# hm11.net
KiCad netlist of a schematic drawn in EAGLE
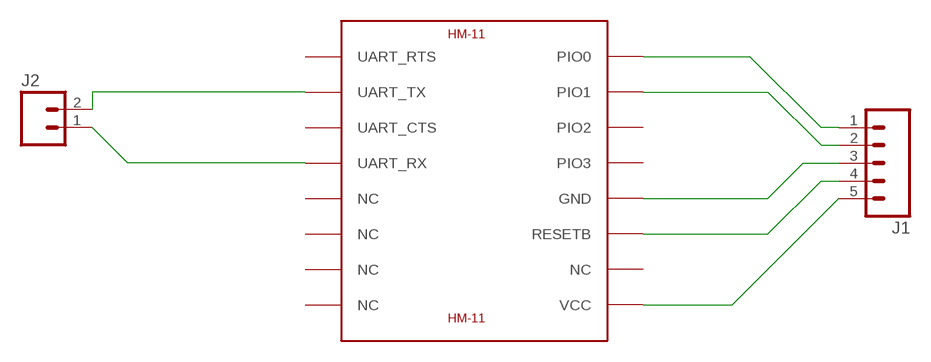
[diagram p0: schematic, sheet 1]

(export (version "E")
  (design (tool "Eeschema 10.0.6"))
  (components
    (comp (ref "J1")
      (value "M05PTH_LONGPADS")
      (footprint "eagle-import:1X05_LONGPADS")
      (libsource (lib "eagle-import") (part "M05PTH_LONGPADS"))
    )
    (comp (ref "J2")
      (value "M02PTH3")
      (footprint "eagle-import:1X02_LONGPADS")
      (libsource (lib "eagle-import") (part "M02PTH3"))
    )
    (comp (ref "U$1")
      (value "HM-11")
      (footprint "eagle-import:HM-11")
      (libsource (lib "eagle-import") (part "HM-11"))
    )
  )
  (nets
    (net (code "1") (name "Net-(J1-Pad1)") (class "Default")
      (node (ref "J1") (pin "1") (pinfunction "1_1") (pintype "passive"))
      (node (ref "U$1") (pin "PIO0") (pinfunction "PIO0_PIO0") (pintype "bidirectional"))
    )
    (net (code "2") (name "Net-(J1-Pad2)") (class "Default")
      (node (ref "J1") (pin "2") (pinfunction "2_2") (pintype "passive"))
      (node (ref "U$1") (pin "PIO1") (pinfunction "PIO1_PIO1") (pintype "bidirectional"))
    )
    (net (code "3") (name "Net-(J1-Pad3)") (class "Default")
      (node (ref "J1") (pin "3") (pinfunction "3_3") (pintype "passive"))
      (node (ref "U$1") (pin "GND") (pinfunction "GND_GND") (pintype "bidirectional"))
    )
    (net (code "4") (name "Net-(J1-Pad4)") (class "Default")
      (node (ref "J1") (pin "4") (pinfunction "4_4") (pintype "passive"))
      (node (ref "U$1") (pin "RESETB") (pinfunction "RESETB_RESETB") (pintype "bidirectional"))
    )
    (net (code "5") (name "Net-(J1-Pad5)") (class "Default")
      (node (ref "J1") (pin "5") (pinfunction "5_5") (pintype "passive"))
      (node (ref "U$1") (pin "VCC") (pinfunction "VCC_VCC") (pintype "bidirectional"))
    )
    (net (code "6") (name "Net-(J2-Pad1)") (class "Default")
      (node (ref "J2") (pin "1") (pinfunction "1_1") (pintype "passive"))
      (node (ref "U$1") (pin "UART_RX") (pinfunction "UART_RX_UART_RX") (pintype "bidirectional"))
    )
    (net (code "7") (name "Net-(J2-Pad2)") (class "Default")
      (node (ref "J2") (pin "2") (pinfunction "2_2") (pintype "passive"))
      (node (ref "U$1") (pin "UART_TX") (pinfunction "UART_TX_UART_TX") (pintype "bidirectional"))
    )
    (net (code "8") (name "unconnected-(U$1-NC-PadNC@5)") (class "Default")
      (node (ref "U$1") (pin "NC@5") (pinfunction "NC_NC@5") (pintype "bidirectional"))
    )
    (net (code "9") (name "unconnected-(U$1-NC-PadNC@6)") (class "Default")
      (node (ref "U$1") (pin "NC@6") (pinfunction "NC_NC@6") (pintype "bidirectional"))
    )
    (net (code "10") (name "unconnected-(U$1-NC-PadNC@7)") (class "Default")
      (node (ref "U$1") (pin "NC@7") (pinfunction "NC_NC@7") (pintype "bidirectional"))
    )
    (net (code "11") (name "unconnected-(U$1-NC-PadNC@8)") (class "Default")
      (node (ref "U$1") (pin "NC@8") (pinfunction "NC_NC@8") (pintype "bidirectional"))
    )
    (net (code "12") (name "unconnected-(U$1-NC-PadNC@10)") (class "Default")
      (node (ref "U$1") (pin "NC@10") (pinfunction "NC_NC@10") (pintype "bidirectional"))
    )
    (net (code "13") (name "unconnected-(U$1-PadPIO2)") (class "Default")
      (node (ref "U$1") (pin "PIO2") (pinfunction "PIO2_PIO2") (pintype "bidirectional"))
    )
    (net (code "14") (name "unconnected-(U$1-PadPIO3)") (class "Default")
      (node (ref "U$1") (pin "PIO3") (pinfunction "PIO3_PIO3") (pintype "bidirectional"))
    )
    (net (code "15") (name "unconnected-(U$1-PadUART_CTS)") (class "Default")
      (node (ref "U$1") (pin "UART_CTS") (pinfunction "UART_CTS_UART_CTS") (pintype "bidirectional"))
    )
    (net (code "16") (name "unconnected-(U$1-PadUART_RTS)") (class "Default")
      (node (ref "U$1") (pin "UART_RTS") (pinfunction "UART_RTS_UART_RTS") (pintype "bidirectional"))
    )
  )
)
